# half.net
KiCad netlist of a schematic drawn in EAGLE
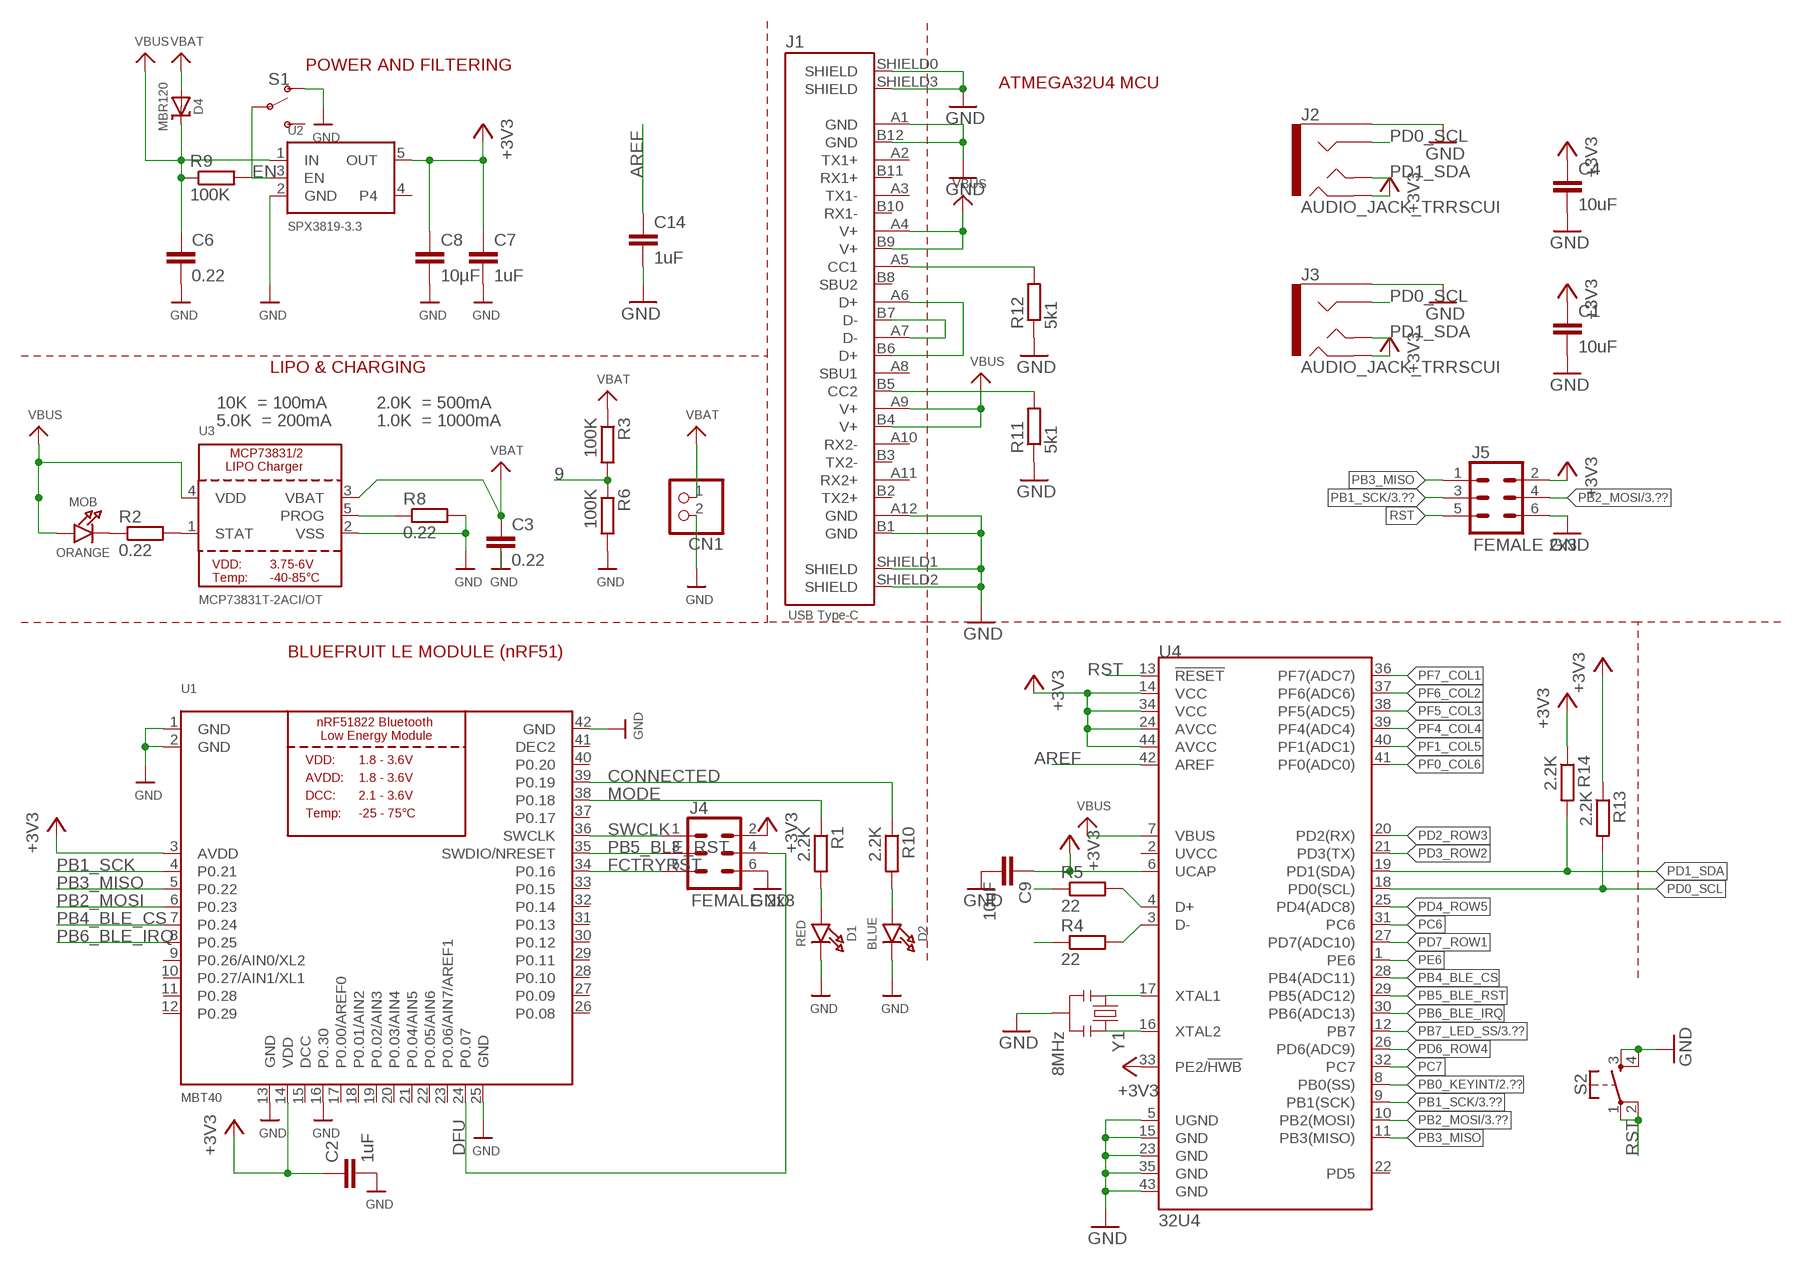
[diagram p0: schematic, sheet 1]
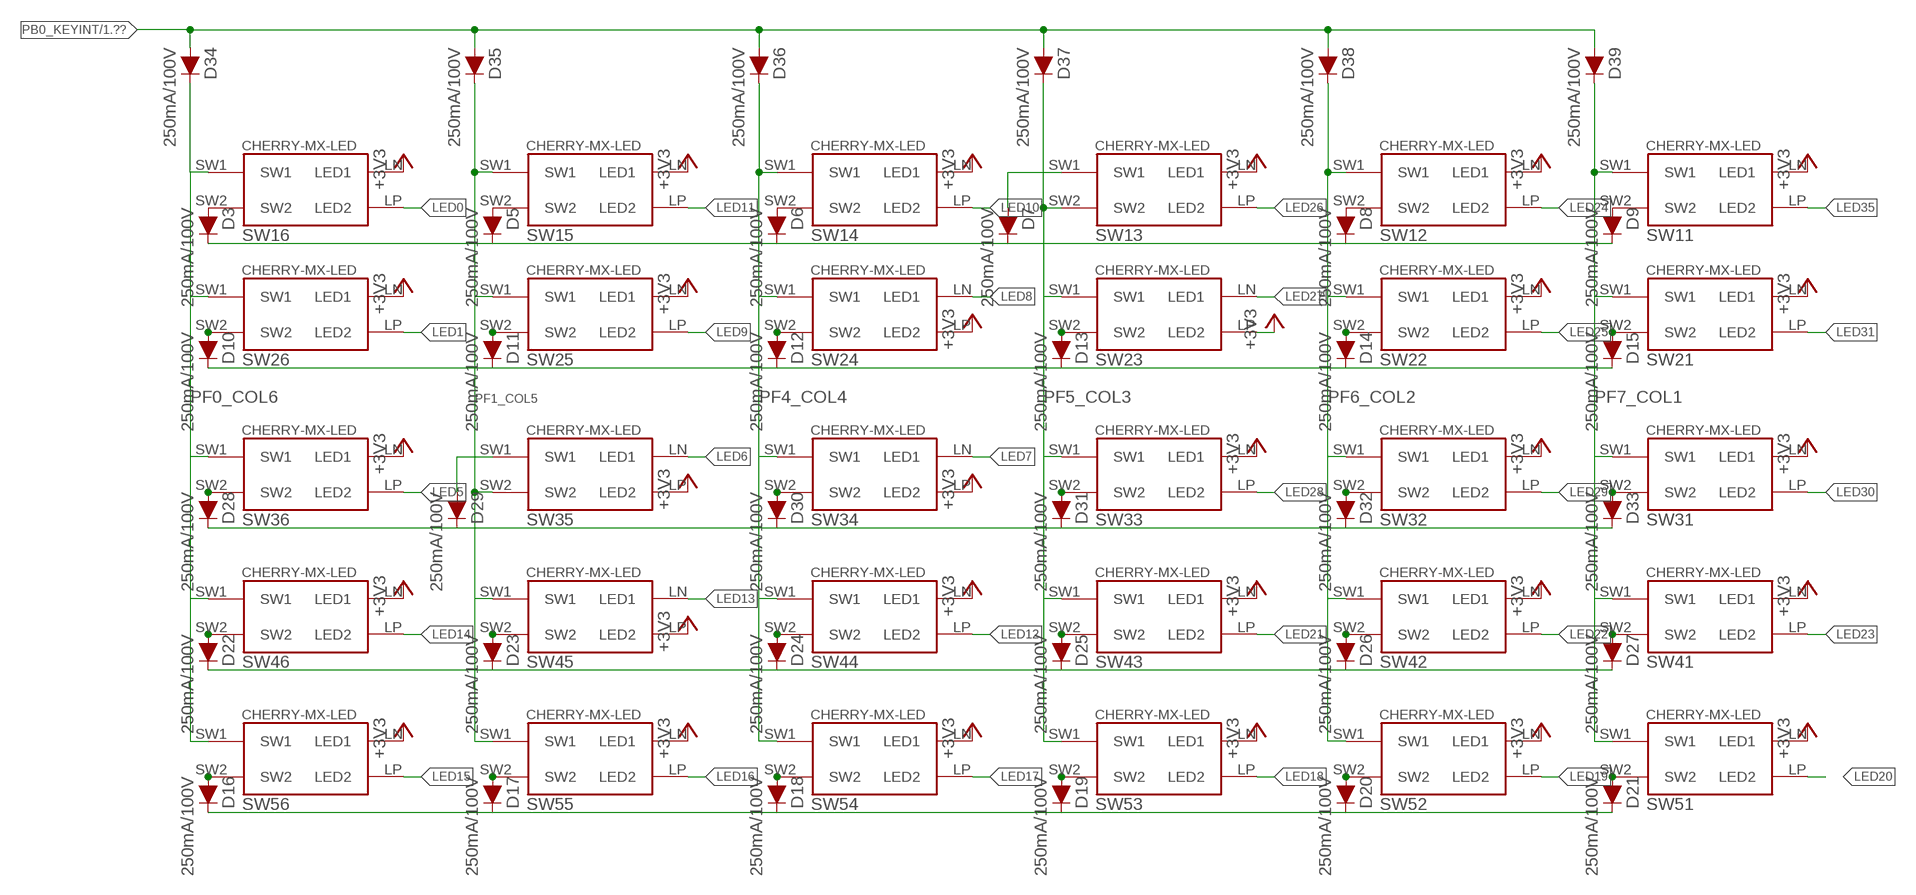
[diagram p1: schematic, sheet 2]
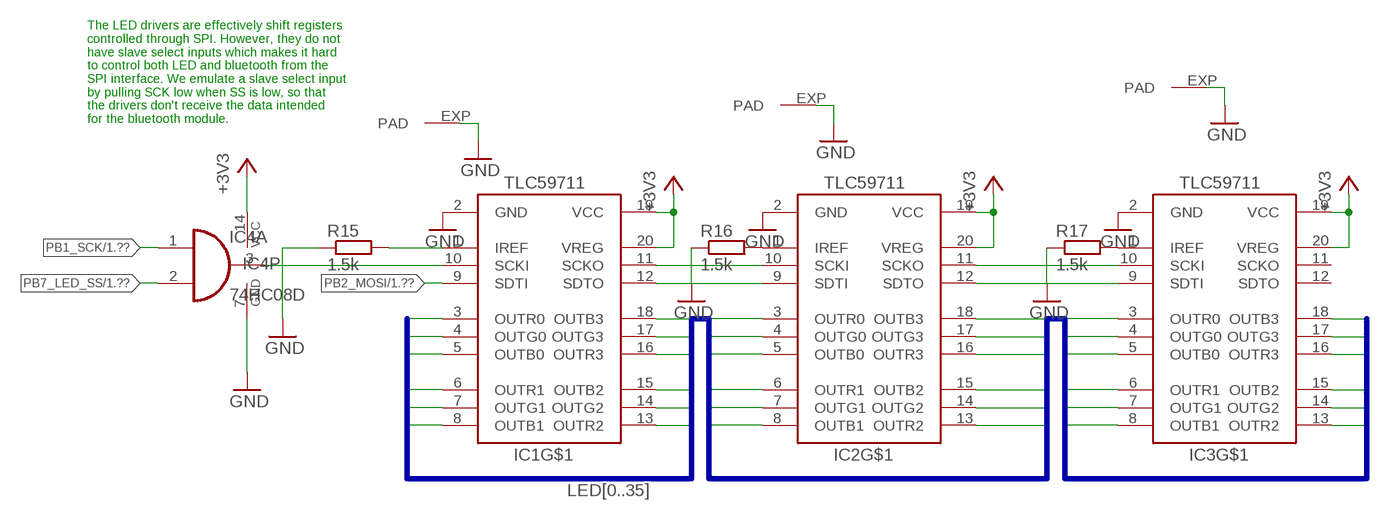
[diagram p2: schematic, sheet 3]

(export (version "E")
  (design (tool "Eeschema 10.0.6"))
  (components
    (comp (ref "D3")
      (value "250mA/100V")
      (footprint "eagle-import:SOD-323")
      (libsource (lib "eagle-import") (part "DIODE-BAS16J"))
    )
    (comp (ref "D5")
      (value "250mA/100V")
      (footprint "eagle-import:SOD-323")
      (libsource (lib "eagle-import") (part "DIODE-BAS16J"))
    )
    (comp (ref "D6")
      (value "250mA/100V")
      (footprint "eagle-import:SOD-323")
      (libsource (lib "eagle-import") (part "DIODE-BAS16J"))
    )
    (comp (ref "D7")
      (value "250mA/100V")
      (footprint "eagle-import:SOD-323")
      (libsource (lib "eagle-import") (part "DIODE-BAS16J"))
    )
    (comp (ref "D8")
      (value "250mA/100V")
      (footprint "eagle-import:SOD-323")
      (libsource (lib "eagle-import") (part "DIODE-BAS16J"))
    )
    (comp (ref "D9")
      (value "250mA/100V")
      (footprint "eagle-import:SOD-323")
      (libsource (lib "eagle-import") (part "DIODE-BAS16J"))
    )
    (comp (ref "D10")
      (value "250mA/100V")
      (footprint "eagle-import:SOD-323")
      (libsource (lib "eagle-import") (part "DIODE-BAS16J"))
    )
    (comp (ref "D11")
      (value "250mA/100V")
      (footprint "eagle-import:SOD-323")
      (libsource (lib "eagle-import") (part "DIODE-BAS16J"))
    )
    (comp (ref "D12")
      (value "250mA/100V")
      (footprint "eagle-import:SOD-323")
      (libsource (lib "eagle-import") (part "DIODE-BAS16J"))
    )
    (comp (ref "D13")
      (value "250mA/100V")
      (footprint "eagle-import:SOD-323")
      (libsource (lib "eagle-import") (part "DIODE-BAS16J"))
    )
    (comp (ref "D14")
      (value "250mA/100V")
      (footprint "eagle-import:SOD-323")
      (libsource (lib "eagle-import") (part "DIODE-BAS16J"))
    )
    (comp (ref "D15")
      (value "250mA/100V")
      (footprint "eagle-import:SOD-323")
      (libsource (lib "eagle-import") (part "DIODE-BAS16J"))
    )
    (comp (ref "D16")
      (value "250mA/100V")
      (footprint "eagle-import:SOD-323")
      (libsource (lib "eagle-import") (part "DIODE-BAS16J"))
    )
    (comp (ref "D17")
      (value "250mA/100V")
      (footprint "eagle-import:SOD-323")
      (libsource (lib "eagle-import") (part "DIODE-BAS16J"))
    )
    (comp (ref "D18")
      (value "250mA/100V")
      (footprint "eagle-import:SOD-323")
      (libsource (lib "eagle-import") (part "DIODE-BAS16J"))
    )
    (comp (ref "D19")
      (value "250mA/100V")
      (footprint "eagle-import:SOD-323")
      (libsource (lib "eagle-import") (part "DIODE-BAS16J"))
    )
    (comp (ref "D20")
      (value "250mA/100V")
      (footprint "eagle-import:SOD-323")
      (libsource (lib "eagle-import") (part "DIODE-BAS16J"))
    )
    (comp (ref "D21")
      (value "250mA/100V")
      (footprint "eagle-import:SOD-323")
      (libsource (lib "eagle-import") (part "DIODE-BAS16J"))
    )
    (comp (ref "D22")
      (value "250mA/100V")
      (footprint "eagle-import:SOD-323")
      (libsource (lib "eagle-import") (part "DIODE-BAS16J"))
    )
    (comp (ref "D23")
      (value "250mA/100V")
      (footprint "eagle-import:SOD-323")
      (libsource (lib "eagle-import") (part "DIODE-BAS16J"))
    )
    (comp (ref "D24")
      (value "250mA/100V")
      (footprint "eagle-import:SOD-323")
      (libsource (lib "eagle-import") (part "DIODE-BAS16J"))
    )
    (comp (ref "D25")
      (value "250mA/100V")
      (footprint "eagle-import:SOD-323")
      (libsource (lib "eagle-import") (part "DIODE-BAS16J"))
    )
    (comp (ref "D26")
      (value "250mA/100V")
      (footprint "eagle-import:SOD-323")
      (libsource (lib "eagle-import") (part "DIODE-BAS16J"))
    )
    (comp (ref "D27")
      (value "250mA/100V")
      (footprint "eagle-import:SOD-323")
      (libsource (lib "eagle-import") (part "DIODE-BAS16J"))
    )
    (comp (ref "D28")
      (value "250mA/100V")
      (footprint "eagle-import:SOD-323")
      (libsource (lib "eagle-import") (part "DIODE-BAS16J"))
    )
    (comp (ref "D29")
      (value "250mA/100V")
      (footprint "eagle-import:SOD-323")
      (libsource (lib "eagle-import") (part "DIODE-BAS16J"))
    )
    (comp (ref "D30")
      (value "250mA/100V")
      (footprint "eagle-import:SOD-323")
      (libsource (lib "eagle-import") (part "DIODE-BAS16J"))
    )
    (comp (ref "D31")
      (value "250mA/100V")
      (footprint "eagle-import:SOD-323")
      (libsource (lib "eagle-import") (part "DIODE-BAS16J"))
    )
    (comp (ref "D32")
      (value "250mA/100V")
      (footprint "eagle-import:SOD-323")
      (libsource (lib "eagle-import") (part "DIODE-BAS16J"))
    )
    (comp (ref "D33")
      (value "250mA/100V")
      (footprint "eagle-import:SOD-323")
      (libsource (lib "eagle-import") (part "DIODE-BAS16J"))
    )
    (comp (ref "D34")
      (value "250mA/100V")
      (footprint "eagle-import:SOD-323")
      (libsource (lib "eagle-import") (part "DIODE-BAS16J"))
    )
    (comp (ref "D35")
      (value "250mA/100V")
      (footprint "eagle-import:SOD-323")
      (libsource (lib "eagle-import") (part "DIODE-BAS16J"))
    )
    (comp (ref "D36")
      (value "250mA/100V")
      (footprint "eagle-import:SOD-323")
      (libsource (lib "eagle-import") (part "DIODE-BAS16J"))
    )
    (comp (ref "D37")
      (value "250mA/100V")
      (footprint "eagle-import:SOD-323")
      (libsource (lib "eagle-import") (part "DIODE-BAS16J"))
    )
    (comp (ref "D38")
      (value "250mA/100V")
      (footprint "eagle-import:SOD-323")
      (libsource (lib "eagle-import") (part "DIODE-BAS16J"))
    )
    (comp (ref "D39")
      (value "250mA/100V")
      (footprint "eagle-import:SOD-323")
      (libsource (lib "eagle-import") (part "DIODE-BAS16J"))
    )
    (comp (ref "SW11")
      (value "CHERRY-MX-LEDSMD")
      (footprint "eagle-import:CHERRY-MX-PM-SMDLED")
      (libsource (lib "eagle-import") (part "CHERRY-MX-LEDSMD"))
    )
    (comp (ref "SW12")
      (value "CHERRY-MX-LEDSMD")
      (footprint "eagle-import:CHERRY-MX-PM-SMDLED")
      (libsource (lib "eagle-import") (part "CHERRY-MX-LEDSMD"))
    )
    (comp (ref "SW13")
      (value "CHERRY-MX-LEDSMD")
      (footprint "eagle-import:CHERRY-MX-PM-SMDLED")
      (libsource (lib "eagle-import") (part "CHERRY-MX-LEDSMD"))
    )
    (comp (ref "SW14")
      (value "CHERRY-MX-LEDSMD")
      (footprint "eagle-import:CHERRY-MX-PM-SMDLED")
      (libsource (lib "eagle-import") (part "CHERRY-MX-LEDSMD"))
    )
    (comp (ref "SW15")
      (value "CHERRY-MX-LEDSMD")
      (footprint "eagle-import:CHERRY-MX-PM-SMDLED")
      (libsource (lib "eagle-import") (part "CHERRY-MX-LEDSMD"))
    )
    (comp (ref "SW16")
      (value "CHERRY-MX-LEDSMD")
      (footprint "eagle-import:CHERRY-MX-PM-SMDLED")
      (libsource (lib "eagle-import") (part "CHERRY-MX-LEDSMD"))
    )
    (comp (ref "SW21")
      (value "CHERRY-MX-LEDSMD")
      (footprint "eagle-import:CHERRY-MX-PM-SMDLED")
      (libsource (lib "eagle-import") (part "CHERRY-MX-LEDSMD"))
    )
    (comp (ref "SW22")
      (value "CHERRY-MX-LEDSMD")
      (footprint "eagle-import:CHERRY-MX-PM-SMDLED")
      (libsource (lib "eagle-import") (part "CHERRY-MX-LEDSMD"))
    )
    (comp (ref "SW23")
      (value "CHERRY-MX-LEDSMD")
      (footprint "eagle-import:CHERRY-MX-PM-SMDLED")
      (libsource (lib "eagle-import") (part "CHERRY-MX-LEDSMD"))
    )
    (comp (ref "SW24")
      (value "CHERRY-MX-LEDSMD")
      (footprint "eagle-import:CHERRY-MX-PM-SMDLED")
      (libsource (lib "eagle-import") (part "CHERRY-MX-LEDSMD"))
    )
    (comp (ref "SW25")
      (value "CHERRY-MX-LEDSMD")
      (footprint "eagle-import:CHERRY-MX-PM-SMDLED")
      (libsource (lib "eagle-import") (part "CHERRY-MX-LEDSMD"))
    )
    (comp (ref "SW26")
      (value "CHERRY-MX-LEDSMD")
      (footprint "eagle-import:CHERRY-MX-PM-SMDLED")
      (libsource (lib "eagle-import") (part "CHERRY-MX-LEDSMD"))
    )
    (comp (ref "SW31")
      (value "CHERRY-MX-LEDSMD")
      (footprint "eagle-import:CHERRY-MX-PM-SMDLED")
      (libsource (lib "eagle-import") (part "CHERRY-MX-LEDSMD"))
    )
    (comp (ref "SW32")
      (value "CHERRY-MX-LEDSMD")
      (footprint "eagle-import:CHERRY-MX-PM-SMDLED")
      (libsource (lib "eagle-import") (part "CHERRY-MX-LEDSMD"))
    )
    (comp (ref "SW33")
      (value "CHERRY-MX-LEDSMD")
      (footprint "eagle-import:CHERRY-MX-PM-SMDLED")
      (libsource (lib "eagle-import") (part "CHERRY-MX-LEDSMD"))
    )
    (comp (ref "SW34")
      (value "CHERRY-MX-LEDSMD")
      (footprint "eagle-import:CHERRY-MX-PM-SMDLED")
      (libsource (lib "eagle-import") (part "CHERRY-MX-LEDSMD"))
    )
    (comp (ref "SW35")
      (value "CHERRY-MX-LEDSMD")
      (footprint "eagle-import:CHERRY-MX-PM-SMDLED")
      (libsource (lib "eagle-import") (part "CHERRY-MX-LEDSMD"))
    )
    (comp (ref "SW36")
      (value "CHERRY-MX-LEDSMD")
      (footprint "eagle-import:CHERRY-MX-PM-SMDLED")
      (libsource (lib "eagle-import") (part "CHERRY-MX-LEDSMD"))
    )
    (comp (ref "SW41")
      (value "CHERRY-MX-LEDSMD")
      (footprint "eagle-import:CHERRY-MX-PM-SMDLED")
      (libsource (lib "eagle-import") (part "CHERRY-MX-LEDSMD"))
    )
    (comp (ref "SW42")
      (value "CHERRY-MX-LEDSMD")
      (footprint "eagle-import:CHERRY-MX-PM-SMDLED")
      (libsource (lib "eagle-import") (part "CHERRY-MX-LEDSMD"))
    )
    (comp (ref "SW43")
      (value "CHERRY-MX-LEDSMD")
      (footprint "eagle-import:CHERRY-MX-PM-SMDLED")
      (libsource (lib "eagle-import") (part "CHERRY-MX-LEDSMD"))
    )
    (comp (ref "SW44")
      (value "CHERRY-MX-LEDSMD")
      (footprint "eagle-import:CHERRY-MX-PM-SMDLED")
      (libsource (lib "eagle-import") (part "CHERRY-MX-LEDSMD"))
    )
    (comp (ref "SW45")
      (value "CHERRY-MX-LEDSMD")
      (footprint "eagle-import:CHERRY-MX-PM-SMDLED")
      (libsource (lib "eagle-import") (part "CHERRY-MX-LEDSMD"))
    )
    (comp (ref "SW46")
      (value "CHERRY-MX-LEDSMD")
      (footprint "eagle-import:CHERRY-MX-PM-SMDLED")
      (libsource (lib "eagle-import") (part "CHERRY-MX-LEDSMD"))
    )
    (comp (ref "SW51")
      (value "CHERRY-MX-LEDSMD")
      (footprint "eagle-import:CHERRY-MX-PM-SMDLED")
      (libsource (lib "eagle-import") (part "CHERRY-MX-LEDSMD"))
    )
    (comp (ref "SW52")
      (value "CHERRY-MX-LEDSMD")
      (footprint "eagle-import:CHERRY-MX-PM-SMDLED")
      (libsource (lib "eagle-import") (part "CHERRY-MX-LEDSMD"))
    )
    (comp (ref "SW53")
      (value "CHERRY-MX-LEDSMD")
      (footprint "eagle-import:CHERRY-MX-PM-SMDLED")
      (libsource (lib "eagle-import") (part "CHERRY-MX-LEDSMD"))
    )
    (comp (ref "SW54")
      (value "CHERRY-MX-LEDSMD")
      (footprint "eagle-import:CHERRY-MX-PM-SMDLED")
      (libsource (lib "eagle-import") (part "CHERRY-MX-LEDSMD"))
    )
    (comp (ref "SW55")
      (value "CHERRY-MX-LEDSMD")
      (footprint "eagle-import:CHERRY-MX-PM-SMDLED")
      (libsource (lib "eagle-import") (part "CHERRY-MX-LEDSMD"))
    )
    (comp (ref "SW56")
      (value "CHERRY-MX-LEDSMD")
      (footprint "eagle-import:CHERRY-MX-PM-SMDLED")
      (libsource (lib "eagle-import") (part "CHERRY-MX-LEDSMD"))
    )
    (comp (ref "IC1")
      (value "TLC59711")
      (footprint "eagle-import:HTSSOP20DAP")
      (libsource (lib "eagle-import") (part "TLC59711"))
    )
    (comp (ref "IC2")
      (value "TLC59711")
      (footprint "eagle-import:HTSSOP20DAP")
      (libsource (lib "eagle-import") (part "TLC59711"))
    )
    (comp (ref "IC3")
      (value "TLC59711")
      (footprint "eagle-import:HTSSOP20DAP")
      (libsource (lib "eagle-import") (part "TLC59711"))
    )
    (comp (ref "IC4")
      (value "74HC08D")
      (footprint "eagle-import:SO14")
      (libsource (lib "eagle-import") (part "7408DHC"))
    )
    (comp (ref "R15")
      (value "1.5k")
      (footprint "eagle-import:R0805")
      (libsource (lib "eagle-import") (part "R-EU_R0805"))
    )
    (comp (ref "R16")
      (value "1.5k")
      (footprint "eagle-import:R0805")
      (libsource (lib "eagle-import") (part "R-EU_R0805"))
    )
    (comp (ref "R17")
      (value "1.5k")
      (footprint "eagle-import:R0805")
      (libsource (lib "eagle-import") (part "R-EU_R0805"))
    )
    (comp (ref "C1")
      (value "10uF")
      (footprint "eagle-import:C0805")
      (libsource (lib "eagle-import") (part "C-EUC0805"))
    )
    (comp (ref "C2")
      (value "1uF")
      (footprint "eagle-import:C0805")
      (libsource (lib "eagle-import") (part "C-EUC0805"))
    )
    (comp (ref "C3")
      (value "0.22")
      (footprint "eagle-import:C0805")
      (libsource (lib "eagle-import") (part "C-EUC0805"))
    )
    (comp (ref "C4")
      (value "10uF")
      (footprint "eagle-import:C0805")
      (libsource (lib "eagle-import") (part "C-EUC0805"))
    )
    (comp (ref "C6")
      (value "0.22")
      (footprint "eagle-import:C0805")
      (libsource (lib "eagle-import") (part "C-EUC0805"))
    )
    (comp (ref "C7")
      (value "1uF")
      (footprint "eagle-import:C0805")
      (libsource (lib "eagle-import") (part "C-EUC0805"))
    )
    (comp (ref "C8")
      (value "10µF")
      (footprint "eagle-import:C0805")
      (libsource (lib "eagle-import") (part "C-EUC0805"))
    )
    (comp (ref "C9")
      (value "10uF")
      (footprint "eagle-import:C0805")
      (libsource (lib "eagle-import") (part "C-EUC0805"))
    )
    (comp (ref "C14")
      (value "1uF")
      (footprint "eagle-import:C0805")
      (libsource (lib "eagle-import") (part "C-EUC0805"))
    )
    (comp (ref "CN1")
      (value "JST_2PIN-SMT-RA")
      (footprint "eagle-import:JST-PH-2-SMT-RA")
      (libsource (lib "eagle-import") (part "JST_2PIN-SMT-RA"))
    )
    (comp (ref "D1")
      (value "RED")
      (footprint "eagle-import:CHIPLED_0805_NOOUTLINE")
      (libsource (lib "eagle-import") (part "LED0805_NOOUTLINE"))
    )
    (comp (ref "D2")
      (value "BLUE")
      (footprint "eagle-import:CHIPLED_0805_NOOUTLINE")
      (libsource (lib "eagle-import") (part "LED0805_NOOUTLINE"))
    )
    (comp (ref "D4")
      (value "MBR120")
      (footprint "eagle-import:SOD-123")
      (libsource (lib "eagle-import") (part "DIODE-SCHOTTKYSOD-123"))
    )
    (comp (ref "J1")
      (value "DX07S024JJ2_USB_TYPE-C")
      (footprint "eagle-import:DX07S0224JJ2_USB-C")
      (fields (field (name "MANF") "USB Type-C DX07 Series Receptacle"))
      (libsource (lib "eagle-import") (part "DX07S024JJ2_USB_TYPE-C"))
    )
    (comp (ref "J2")
      (value "AUDIO_JACK_TRRSCUI")
      (footprint "eagle-import:AUDIO_JACK_3.5MM_TRRS_SMD_CUI")
      (libsource (lib "eagle-import") (part "AUDIO_JACK_TRRSCUI"))
    )
    (comp (ref "J3")
      (value "AUDIO_JACK_TRRSCUI")
      (footprint "eagle-import:AUDIO_JACK_3.5MM_TRRS_SMD_CUI")
      (libsource (lib "eagle-import") (part "AUDIO_JACK_TRRSCUI"))
    )
    (comp (ref "J4")
      (value "FEMALE 2x3")
      (footprint "eagle-import:2X3")
      (libsource (lib "eagle-import") (part "CONN_03X2FEMALE"))
    )
    (comp (ref "J5")
      (value "FEMALE 2x3")
      (footprint "eagle-import:2X3")
      (libsource (lib "eagle-import") (part "CONN_03X2FEMALE"))
    )
    (comp (ref "MOB")
      (value "ORANGE")
      (footprint "eagle-import:CHIPLED_0805_NOOUTLINE")
      (libsource (lib "eagle-import") (part "LED0805_NOOUTLINE"))
    )
    (comp (ref "R1")
      (value "2.2K")
      (footprint "eagle-import:R0805")
      (libsource (lib "eagle-import") (part "R-EU_R0805"))
    )
    (comp (ref "R2")
      (value "0.22")
      (footprint "eagle-import:R0805")
      (libsource (lib "eagle-import") (part "R-EU_R0805"))
    )
    (comp (ref "R3")
      (value "100K")
      (footprint "eagle-import:R0805")
      (libsource (lib "eagle-import") (part "R-EU_R0805"))
    )
    (comp (ref "R4")
      (value "22")
      (footprint "eagle-import:R0805")
      (libsource (lib "eagle-import") (part "R-EU_R0805"))
    )
    (comp (ref "R5")
      (value "22")
      (footprint "eagle-import:R0805")
      (libsource (lib "eagle-import") (part "R-EU_R0805"))
    )
    (comp (ref "R6")
      (value "100K")
      (footprint "eagle-import:R0805")
      (libsource (lib "eagle-import") (part "R-EU_R0805"))
    )
    (comp (ref "R8")
      (value "0.22")
      (footprint "eagle-import:R0805")
      (libsource (lib "eagle-import") (part "R-EU_R0805"))
    )
    (comp (ref "R9")
      (value "100K")
      (footprint "eagle-import:R0805")
      (libsource (lib "eagle-import") (part "R-EU_R0805"))
    )
    (comp (ref "R10")
      (value "2.2K")
      (footprint "eagle-import:R0805")
      (libsource (lib "eagle-import") (part "R-EU_R0805"))
    )
    (comp (ref "R11")
      (value "5k1")
      (footprint "eagle-import:R0805")
      (libsource (lib "eagle-import") (part "R-EU_R0805"))
    )
    (comp (ref "R12")
      (value "5k1")
      (footprint "eagle-import:R0805")
      (libsource (lib "eagle-import") (part "R-EU_R0805"))
    )
    (comp (ref "R13")
      (value "2.2K")
      (footprint "eagle-import:R0805")
      (libsource (lib "eagle-import") (part "R-EU_R0805"))
    )
    (comp (ref "R14")
      (value "2.2K")
      (footprint "eagle-import:R0805")
      (libsource (lib "eagle-import") (part "R-EU_R0805"))
    )
    (comp (ref "S1")
      (value "SWITCH-SPDT-SMD-RIGHT-ANGLE")
      (footprint "eagle-import:SWITCH_SPST_SMD_A")
      (libsource (lib "eagle-import") (part "SWITCH-SPDT-SMD-RIGHT-ANGLE"))
    )
    (comp (ref "S2")
      (value "MOMENTARY-SWITCH-SPST-2-SMD-5.2MM")
      (footprint "eagle-import:TACTILE_SWITCH_SMD_5.2MM")
      (libsource (lib "eagle-import") (part "MOMENTARY-SWITCH-SPST-2-SMD-5.2MM"))
    )
    (comp (ref "U1")
      (value "MBT40")
      (footprint "eagle-import:BLE_MODULE_RAYTAC_MDBT40")
      (libsource (lib "eagle-import") (part "NRF51822_MODULE_MDBT40"))
    )
    (comp (ref "U2")
      (value "SPX3819-3.3")
      (footprint "eagle-import:SOT23-5")
      (libsource (lib "eagle-import") (part "VREG_SOT23-5"))
    )
    (comp (ref "U3")
      (value "MCP73831T-2ACI/OT")
      (footprint "eagle-import:SOT23-5")
      (libsource (lib "eagle-import") (part "MCP73831/2"))
    )
    (comp (ref "U4")
      (value "32U4")
      (footprint "eagle-import:TQFP44")
      (libsource (lib "eagle-import") (part "ATMEGA32U4TQFP-44"))
    )
    (comp (ref "Y1")
      (value "8MHz")
      (footprint "eagle-import:RESONATOR-SMD")
      (libsource (lib "eagle-import") (part "RESONATORSMD"))
    )
  )
  (nets
    (net (code "7") (name "+3V3") (class "Default")
      (node (ref "C1") (pin "1") (pinfunction "1_1") (pintype "passive"))
      (node (ref "C2") (pin "1") (pinfunction "1_1") (pintype "passive"))
      (node (ref "C4") (pin "1") (pinfunction "1_1") (pintype "passive"))
      (node (ref "C7") (pin "1") (pinfunction "1_1") (pintype "passive"))
      (node (ref "C8") (pin "1") (pinfunction "1_1") (pintype "passive"))
      (node (ref "C9") (pin "1") (pinfunction "1_1") (pintype "passive"))
      (node (ref "IC1") (pin "19") (pinfunction "VCC_19") (pintype "power_in"))
      (node (ref "IC1") (pin "20") (pinfunction "VREG_20") (pintype "bidirectional"))
      (node (ref "IC2") (pin "19") (pinfunction "VCC_19") (pintype "power_in"))
      (node (ref "IC2") (pin "20") (pinfunction "VREG_20") (pintype "bidirectional"))
      (node (ref "IC3") (pin "19") (pinfunction "VCC_19") (pintype "power_in"))
      (node (ref "IC3") (pin "20") (pinfunction "VREG_20") (pintype "bidirectional"))
      (node (ref "IC4") (pin "14") (pinfunction "VCC_14") (pintype "power_in"))
      (node (ref "J2") (pin "RING2") (pinfunction "RING2_RING2") (pintype "bidirectional"))
      (node (ref "J3") (pin "RING2") (pinfunction "RING2_RING2") (pintype "bidirectional"))
      (node (ref "J4") (pin "2") (pinfunction "2_2") (pintype "bidirectional"))
      (node (ref "J5") (pin "2") (pinfunction "2_2") (pintype "bidirectional"))
      (node (ref "R13") (pin "1") (pinfunction "1_1") (pintype "passive"))
      (node (ref "R14") (pin "1") (pinfunction "1_1") (pintype "passive"))
      (node (ref "SW11") (pin "LN") (pinfunction "LED1_LN") (pintype "bidirectional"))
      (node (ref "SW12") (pin "LN") (pinfunction "LED1_LN") (pintype "bidirectional"))
      (node (ref "SW13") (pin "LN") (pinfunction "LED1_LN") (pintype "bidirectional"))
      (node (ref "SW14") (pin "LN") (pinfunction "LED1_LN") (pintype "bidirectional"))
      (node (ref "SW15") (pin "LN") (pinfunction "LED1_LN") (pintype "bidirectional"))
      (node (ref "SW16") (pin "LN") (pinfunction "LED1_LN") (pintype "bidirectional"))
      (node (ref "SW21") (pin "LN") (pinfunction "LED1_LN") (pintype "bidirectional"))
      (node (ref "SW22") (pin "LN") (pinfunction "LED1_LN") (pintype "bidirectional"))
      (node (ref "SW23") (pin "LP") (pinfunction "LED2_LP") (pintype "bidirectional"))
      (node (ref "SW24") (pin "LP") (pinfunction "LED2_LP") (pintype "bidirectional"))
      (node (ref "SW25") (pin "LN") (pinfunction "LED1_LN") (pintype "bidirectional"))
      (node (ref "SW26") (pin "LN") (pinfunction "LED1_LN") (pintype "bidirectional"))
      (node (ref "SW31") (pin "LN") (pinfunction "LED1_LN") (pintype "bidirectional"))
      (node (ref "SW32") (pin "LN") (pinfunction "LED1_LN") (pintype "bidirectional"))
      (node (ref "SW33") (pin "LN") (pinfunction "LED1_LN") (pintype "bidirectional"))
      (node (ref "SW34") (pin "LP") (pinfunction "LED2_LP") (pintype "bidirectional"))
      (node (ref "SW35") (pin "LP") (pinfunction "LED2_LP") (pintype "bidirectional"))
      (node (ref "SW36") (pin "LN") (pinfunction "LED1_LN") (pintype "bidirectional"))
      (node (ref "SW41") (pin "LN") (pinfunction "LED1_LN") (pintype "bidirectional"))
      (node (ref "SW42") (pin "LN") (pinfunction "LED1_LN") (pintype "bidirectional"))
      (node (ref "SW43") (pin "LN") (pinfunction "LED1_LN") (pintype "bidirectional"))
      (node (ref "SW44") (pin "LN") (pinfunction "LED1_LN") (pintype "bidirectional"))
      (node (ref "SW45") (pin "LP") (pinfunction "LED2_LP") (pintype "bidirectional"))
      (node (ref "SW46") (pin "LN") (pinfunction "LED1_LN") (pintype "bidirectional"))
      (node (ref "SW51") (pin "LN") (pinfunction "LED1_LN") (pintype "bidirectional"))
      (node (ref "SW52") (pin "LN") (pinfunction "LED1_LN") (pintype "bidirectional"))
      (node (ref "SW53") (pin "LN") (pinfunction "LED1_LN") (pintype "bidirectional"))
      (node (ref "SW54") (pin "LN") (pinfunction "LED1_LN") (pintype "bidirectional"))
      (node (ref "SW55") (pin "LN") (pinfunction "LED1_LN") (pintype "bidirectional"))
      (node (ref "SW56") (pin "LN") (pinfunction "LED1_LN") (pintype "bidirectional"))
      (node (ref "U1") (pin "14") (pinfunction "VDD_14") (pintype "power_in"))
      (node (ref "U1") (pin "3") (pinfunction "AVDD_3") (pintype "power_in"))
      (node (ref "U2") (pin "5") (pinfunction "OUT_5") (pintype "power_in"))
      (node (ref "U4") (pin "14") (pinfunction "VCC_14") (pintype "bidirectional"))
      (node (ref "U4") (pin "24") (pinfunction "AVCC_24") (pintype "bidirectional"))
      (node (ref "U4") (pin "33") (pinfunction "PE2/~{HWB}_33") (pintype "bidirectional"))
      (node (ref "U4") (pin "34") (pinfunction "VCC_34") (pintype "bidirectional"))
      (node (ref "U4") (pin "44") (pinfunction "AVCC_44") (pintype "bidirectional"))
      (node (ref "U4") (pin "6") (pinfunction "UCAP_6") (pintype "bidirectional"))
    )
    (net (code "9") (name "9") (class "Default")
      (node (ref "R3") (pin "2") (pinfunction "2_2") (pintype "passive"))
      (node (ref "R6") (pin "1") (pinfunction "1_1") (pintype "passive"))
    )
    (net (code "10") (name "AREF") (class "Default")
      (node (ref "C14") (pin "1") (pinfunction "1_1") (pintype "passive"))
      (node (ref "U4") (pin "42") (pinfunction "AREF_42") (pintype "bidirectional"))
    )
    (net (code "11") (name "CONNECTED") (class "Default")
      (node (ref "R10") (pin "1") (pinfunction "1_1") (pintype "passive"))
      (node (ref "U1") (pin "39") (pinfunction "P0.19_39") (pintype "bidirectional"))
    )
    (net (code "12") (name "D++") (class "Default")
      (node (ref "J1") (pin "A6") (pinfunction "D+_A6") (pintype "bidirectional"))
      (node (ref "J1") (pin "B6") (pinfunction "D+_B6") (pintype "bidirectional"))
      (node (ref "R5") (pin "1") (pinfunction "1_1") (pintype "passive"))
    )
    (net (code "13") (name "D--") (class "Default")
      (node (ref "J1") (pin "A7") (pinfunction "D-_A7") (pintype "bidirectional"))
      (node (ref "J1") (pin "B7") (pinfunction "D-_B7") (pintype "bidirectional"))
      (node (ref "R4") (pin "1") (pinfunction "1_1") (pintype "passive"))
    )
    (net (code "14") (name "DCC") (class "Default")
      (node (ref "U1") (pin "15") (pinfunction "DCC_15") (pintype "power_in"))
    )
    (net (code "15") (name "DEC2") (class "Default")
      (node (ref "U1") (pin "41") (pinfunction "DEC2_41") (pintype "power_in"))
    )
    (net (code "16") (name "DFU") (class "Default")
      (node (ref "J4") (pin "4") (pinfunction "4_4") (pintype "bidirectional"))
      (node (ref "U1") (pin "24") (pinfunction "P0.07_24") (pintype "bidirectional"))
    )
    (net (code "17") (name "EN") (class "Default")
      (node (ref "R9") (pin "2") (pinfunction "2_2") (pintype "passive"))
      (node (ref "S1") (pin "2") (pinfunction "P_2") (pintype "passive"))
      (node (ref "U2") (pin "3") (pinfunction "EN_3") (pintype "input"))
    )
    (net (code "18") (name "FCTRYRST") (class "Default")
      (node (ref "J4") (pin "5") (pinfunction "5_5") (pintype "bidirectional"))
      (node (ref "U1") (pin "34") (pinfunction "P0.16_34") (pintype "bidirectional"))
    )
    (net (code "19") (name "GND") (class "Default")
      (node (ref "C1") (pin "2") (pinfunction "2_2") (pintype "passive"))
      (node (ref "C14") (pin "2") (pinfunction "2_2") (pintype "passive"))
      (node (ref "C2") (pin "2") (pinfunction "2_2") (pintype "passive"))
      (node (ref "C3") (pin "2") (pinfunction "2_2") (pintype "passive"))
      (node (ref "C4") (pin "2") (pinfunction "2_2") (pintype "passive"))
      (node (ref "C6") (pin "2") (pinfunction "2_2") (pintype "passive"))
      (node (ref "C7") (pin "2") (pinfunction "2_2") (pintype "passive"))
      (node (ref "C8") (pin "2") (pinfunction "2_2") (pintype "passive"))
      (node (ref "C9") (pin "2") (pinfunction "2_2") (pintype "passive"))
      (node (ref "CN1") (pin "2") (pinfunction "1_2") (pintype "passive"))
      (node (ref "D1") (pin "C") (pinfunction "C_C") (pintype "passive"))
      (node (ref "D2") (pin "C") (pinfunction "C_C") (pintype "passive"))
      (node (ref "IC1") (pin "2") (pinfunction "GND_2") (pintype "power_in"))
      (node (ref "IC1") (pin "EXP") (pinfunction "PAD_EXP") (pintype "passive"))
      (node (ref "IC2") (pin "2") (pinfunction "GND_2") (pintype "power_in"))
      (node (ref "IC2") (pin "EXP") (pinfunction "PAD_EXP") (pintype "passive"))
      (node (ref "IC3") (pin "2") (pinfunction "GND_2") (pintype "power_in"))
      (node (ref "IC3") (pin "EXP") (pinfunction "PAD_EXP") (pintype "passive"))
      (node (ref "IC4") (pin "7") (pinfunction "GND_7") (pintype "power_in"))
      (node (ref "J1") (pin "A1") (pinfunction "GND_A1") (pintype "power_in"))
      (node (ref "J1") (pin "A12") (pinfunction "GND_A12") (pintype "power_in"))
      (node (ref "J1") (pin "B1") (pinfunction "GND_B1") (pintype "power_in"))
      (node (ref "J1") (pin "B12") (pinfunction "GND_B12") (pintype "power_in"))
      (node (ref "J1") (pin "SHIELD0") (pinfunction "SHIELD_SHIELD0") (pintype "bidirectional"))
      (node (ref "J1") (pin "SHIELD1") (pinfunction "SHIELD_SHIELD1") (pintype "bidirectional"))
      (node (ref "J1") (pin "SHIELD2") (pinfunction "SHIELD_SHIELD2") (pintype "bidirectional"))
      (node (ref "J1") (pin "SHIELD3") (pinfunction "SHIELD_SHIELD3") (pintype "bidirectional"))
      (node (ref "J2") (pin "EARTH") (pinfunction "EARTH_EARTH") (pintype "bidirectional"))
      (node (ref "J3") (pin "EARTH") (pinfunction "EARTH_EARTH") (pintype "bidirectional"))
      (node (ref "J4") (pin "6") (pinfunction "6_6") (pintype "bidirectional"))
      (node (ref "J5") (pin "6") (pinfunction "6_6") (pintype "bidirectional"))
      (node (ref "R11") (pin "1") (pinfunction "1_1") (pintype "passive"))
      (node (ref "R12") (pin "1") (pinfunction "1_1") (pintype "passive"))
      (node (ref "R15") (pin "1") (pinfunction "1_1") (pintype "passive"))
      (node (ref "R16") (pin "1") (pinfunction "1_1") (pintype "passive"))
      (node (ref "R17") (pin "1") (pinfunction "1_1") (pintype "passive"))
      (node (ref "R6") (pin "2") (pinfunction "2_2") (pintype "passive"))
      (node (ref "R8") (pin "2") (pinfunction "2_2") (pintype "passive"))
      (node (ref "S1") (pin "1") (pinfunction "O_1") (pintype "passive"))
      (node (ref "S2") (pin "3") (pinfunction "3_3") (pintype "passive"))
      (node (ref "S2") (pin "4") (pinfunction "4_4") (pintype "passive"))
      (node (ref "U1") (pin "1") (pinfunction "GND_1") (pintype "power_in"))
      (node (ref "U1") (pin "13") (pinfunction "GND_13") (pintype "power_in"))
      (node (ref "U1") (pin "16") (pinfunction "P0.30_16") (pintype "bidirectional"))
      (node (ref "U1") (pin "2") (pinfunction "GND_2") (pintype "power_in"))
      (node (ref "U1") (pin "25") (pinfunction "GND_25") (pintype "power_in"))
      (node (ref "U1") (pin "42") (pinfunction "GND_42") (pintype "power_in"))
      (node (ref "U2") (pin "2") (pinfunction "GND_2") (pintype "power_in"))
      (node (ref "U3") (pin "2") (pinfunction "VSS_2") (pintype "power_in"))
      (node (ref "U4") (pin "15") (pinfunction "GND_15") (pintype "bidirectional"))
      (node (ref "U4") (pin "23") (pinfunction "GND_23") (pintype "bidirectional"))
      (node (ref "U4") (pin "35") (pinfunction "GND_35") (pintype "bidirectional"))
      (node (ref "U4") (pin "43") (pinfunction "GND_43") (pintype "bidirectional"))
      (node (ref "U4") (pin "5") (pinfunction "UGND_5") (pintype "bidirectional"))
      (node (ref "Y1") (pin "2") (pinfunction "2_2") (pintype "passive"))
    )
    (net (code "20") (name "LED0") (class "Default")
      (node (ref "IC1") (pin "3") (pinfunction "OUTR0_3") (pintype "open_collector"))
      (node (ref "SW16") (pin "LP") (pinfunction "LED2_LP") (pintype "bidirectional"))
    )
    (net (code "21") (name "LED1") (class "Default")
      (node (ref "IC1") (pin "4") (pinfunction "OUTG0_4") (pintype "open_collector"))
      (node (ref "SW26") (pin "LP") (pinfunction "LED2_LP") (pintype "bidirectional"))
    )
    (net (code "22") (name "LED5") (class "Default")
      (node (ref "IC1") (pin "8") (pinfunction "OUTB1_8") (pintype "open_collector"))
      (node (ref "SW36") (pin "LP") (pinfunction "LED2_LP") (pintype "bidirectional"))
    )
    (net (code "23") (name "LED6") (class "Default")
      (node (ref "IC1") (pin "13") (pinfunction "OUTR2_13") (pintype "open_collector"))
      (node (ref "SW35") (pin "LN") (pinfunction "LED1_LN") (pintype "bidirectional"))
    )
    (net (code "24") (name "LED7") (class "Default")
      (node (ref "IC1") (pin "14") (pinfunction "OUTG2_14") (pintype "open_collector"))
      (node (ref "SW34") (pin "LN") (pinfunction "LED1_LN") (pintype "bidirectional"))
    )
    (net (code "25") (name "LED8") (class "Default")
      (node (ref "IC1") (pin "15") (pinfunction "OUTB2_15") (pintype "open_collector"))
      (node (ref "SW24") (pin "LN") (pinfunction "LED1_LN") (pintype "bidirectional"))
    )
    (net (code "26") (name "LED9") (class "Default")
      (node (ref "IC1") (pin "16") (pinfunction "OUTR3_16") (pintype "open_collector"))
      (node (ref "SW25") (pin "LP") (pinfunction "LED2_LP") (pintype "bidirectional"))
    )
    (net (code "27") (name "LED10") (class "Default")
      (node (ref "IC1") (pin "17") (pinfunction "OUTG3_17") (pintype "open_collector"))
      (node (ref "SW14") (pin "LP") (pinfunction "LED2_LP") (pintype "bidirectional"))
    )
    (net (code "28") (name "LED11") (class "Default")
      (node (ref "IC1") (pin "18") (pinfunction "OUTB3_18") (pintype "open_collector"))
      (node (ref "SW15") (pin "LP") (pinfunction "LED2_LP") (pintype "bidirectional"))
    )
    (net (code "29") (name "LED12") (class "Default")
      (node (ref "IC2") (pin "3") (pinfunction "OUTR0_3") (pintype "open_collector"))
      (node (ref "SW44") (pin "LP") (pinfunction "LED2_LP") (pintype "bidirectional"))
    )
    (net (code "30") (name "LED13") (class "Default")
      (node (ref "IC2") (pin "4") (pinfunction "OUTG0_4") (pintype "open_collector"))
      (node (ref "SW45") (pin "LN") (pinfunction "LED1_LN") (pintype "bidirectional"))
    )
    (net (code "31") (name "LED14") (class "Default")
      (node (ref "IC2") (pin "5") (pinfunction "OUTB0_5") (pintype "open_collector"))
      (node (ref "SW46") (pin "LP") (pinfunction "LED2_LP") (pintype "bidirectional"))
    )
    (net (code "32") (name "LED15") (class "Default")
      (node (ref "IC2") (pin "6") (pinfunction "OUTR1_6") (pintype "open_collector"))
      (node (ref "SW56") (pin "LP") (pinfunction "LED2_LP") (pintype "bidirectional"))
    )
    (net (code "33") (name "LED16") (class "Default")
      (node (ref "IC2") (pin "7") (pinfunction "OUTG1_7") (pintype "open_collector"))
      (node (ref "SW55") (pin "LP") (pinfunction "LED2_LP") (pintype "bidirectional"))
    )
    (net (code "34") (name "LED17") (class "Default")
      (node (ref "IC2") (pin "8") (pinfunction "OUTB1_8") (pintype "open_collector"))
      (node (ref "SW54") (pin "LP") (pinfunction "LED2_LP") (pintype "bidirectional"))
    )
    (net (code "35") (name "LED18") (class "Default")
      (node (ref "IC2") (pin "13") (pinfunction "OUTR2_13") (pintype "open_collector"))
      (node (ref "SW53") (pin "LP") (pinfunction "LED2_LP") (pintype "bidirectional"))
    )
    (net (code "36") (name "LED19") (class "Default")
      (node (ref "IC2") (pin "14") (pinfunction "OUTG2_14") (pintype "open_collector"))
      (node (ref "SW52") (pin "LP") (pinfunction "LED2_LP") (pintype "bidirectional"))
    )
    (net (code "37") (name "LED20") (class "Default")
      (node (ref "IC2") (pin "15") (pinfunction "OUTB2_15") (pintype "open_collector"))
      (node (ref "SW51") (pin "LP") (pinfunction "LED2_LP") (pintype "bidirectional"))
    )
    (net (code "38") (name "LED21") (class "Default")
      (node (ref "IC2") (pin "16") (pinfunction "OUTR3_16") (pintype "open_collector"))
      (node (ref "SW43") (pin "LP") (pinfunction "LED2_LP") (pintype "bidirectional"))
    )
    (net (code "39") (name "LED22") (class "Default")
      (node (ref "IC2") (pin "17") (pinfunction "OUTG3_17") (pintype "open_collector"))
      (node (ref "SW42") (pin "LP") (pinfunction "LED2_LP") (pintype "bidirectional"))
    )
    (net (code "40") (name "LED23") (class "Default")
      (node (ref "IC2") (pin "18") (pinfunction "OUTB3_18") (pintype "open_collector"))
      (node (ref "SW41") (pin "LP") (pinfunction "LED2_LP") (pintype "bidirectional"))
    )
    (net (code "41") (name "LED24") (class "Default")
      (node (ref "IC3") (pin "3") (pinfunction "OUTR0_3") (pintype "open_collector"))
      (node (ref "SW12") (pin "LP") (pinfunction "LED2_LP") (pintype "bidirectional"))
    )
    (net (code "42") (name "LED25") (class "Default")
      (node (ref "IC3") (pin "4") (pinfunction "OUTG0_4") (pintype "open_collector"))
      (node (ref "SW22") (pin "LP") (pinfunction "LED2_LP") (pintype "bidirectional"))
    )
    (net (code "43") (name "LED26") (class "Default")
      (node (ref "IC3") (pin "5") (pinfunction "OUTB0_5") (pintype "open_collector"))
      (node (ref "SW13") (pin "LP") (pinfunction "LED2_LP") (pintype "bidirectional"))
    )
    (net (code "44") (name "LED27") (class "Default")
      (node (ref "IC3") (pin "6") (pinfunction "OUTR1_6") (pintype "open_collector"))
      (node (ref "SW23") (pin "LN") (pinfunction "LED1_LN") (pintype "bidirectional"))
    )
    (net (code "45") (name "LED28") (class "Default")
      (node (ref "IC3") (pin "7") (pinfunction "OUTG1_7") (pintype "open_collector"))
      (node (ref "SW33") (pin "LP") (pinfunction "LED2_LP") (pintype "bidirectional"))
    )
    (net (code "46") (name "LED29") (class "Default")
      (node (ref "IC3") (pin "8") (pinfunction "OUTB1_8") (pintype "open_collector"))
      (node (ref "SW32") (pin "LP") (pinfunction "LED2_LP") (pintype "bidirectional"))
    )
    (net (code "47") (name "LED30") (class "Default")
      (node (ref "IC3") (pin "13") (pinfunction "OUTR2_13") (pintype "open_collector"))
      (node (ref "SW31") (pin "LP") (pinfunction "LED2_LP") (pintype "bidirectional"))
    )
    (net (code "48") (name "LED31") (class "Default")
      (node (ref "IC3") (pin "14") (pinfunction "OUTG2_14") (pintype "open_collector"))
      (node (ref "SW21") (pin "LP") (pinfunction "LED2_LP") (pintype "bidirectional"))
    )
    (net (code "49") (name "LED35") (class "Default")
      (node (ref "IC3") (pin "18") (pinfunction "OUTB3_18") (pintype "open_collector"))
      (node (ref "SW11") (pin "LP") (pinfunction "LED2_LP") (pintype "bidirectional"))
    )
    (net (code "50") (name "MODE") (class "Default")
      (node (ref "R1") (pin "1") (pinfunction "1_1") (pintype "passive"))
      (node (ref "U1") (pin "38") (pinfunction "P0.18_38") (pintype "bidirectional"))
    )
    (net (code "51") (name "Net-(D1-PadA)") (class "Default")
      (node (ref "D1") (pin "A") (pinfunction "A_A") (pintype "passive"))
      (node (ref "R1") (pin "2") (pinfunction "2_2") (pintype "passive"))
    )
    (net (code "52") (name "Net-(D2-PadA)") (class "Default")
      (node (ref "D2") (pin "A") (pinfunction "A_A") (pintype "passive"))
      (node (ref "R10") (pin "2") (pinfunction "2_2") (pintype "passive"))
    )
    (net (code "53") (name "Net-(D3-PadA)") (class "Default")
      (node (ref "D3") (pin "A") (pinfunction "A_A") (pintype "passive"))
      (node (ref "SW16") (pin "SW2") (pinfunction "SW2_SW2") (pintype "bidirectional"))
    )
    (net (code "54") (name "Net-(D5-PadA)") (class "Default")
      (node (ref "D5") (pin "A") (pinfunction "A_A") (pintype "passive"))
      (node (ref "SW15") (pin "SW2") (pinfunction "SW2_SW2") (pintype "bidirectional"))
    )
    (net (code "55") (name "Net-(D6-PadA)") (class "Default")
      (node (ref "D6") (pin "A") (pinfunction "A_A") (pintype "passive"))
      (node (ref "SW14") (pin "SW2") (pinfunction "SW2_SW2") (pintype "bidirectional"))
    )
    (net (code "56") (name "Net-(D7-PadA)") (class "Default")
      (node (ref "D7") (pin "A") (pinfunction "A_A") (pintype "passive"))
      (node (ref "SW13") (pin "SW1") (pinfunction "SW1_SW1") (pintype "bidirectional"))
    )
    (net (code "57") (name "Net-(D8-PadA)") (class "Default")
      (node (ref "D8") (pin "A") (pinfunction "A_A") (pintype "passive"))
      (node (ref "SW12") (pin "SW2") (pinfunction "SW2_SW2") (pintype "bidirectional"))
    )
    (net (code "58") (name "Net-(D9-PadA)") (class "Default")
      (node (ref "D9") (pin "A") (pinfunction "A_A") (pintype "passive"))
      (node (ref "SW11") (pin "SW2") (pinfunction "SW2_SW2") (pintype "bidirectional"))
    )
    (net (code "59") (name "Net-(D10-PadA)") (class "Default")
      (node (ref "D10") (pin "A") (pinfunction "A_A") (pintype "passive"))
      (node (ref "SW26") (pin "SW2") (pinfunction "SW2_SW2") (pintype "bidirectional"))
    )
    (net (code "60") (name "Net-(D11-PadA)") (class "Default")
      (node (ref "D11") (pin "A") (pinfunction "A_A") (pintype "passive"))
      (node (ref "SW25") (pin "SW2") (pinfunction "SW2_SW2") (pintype "bidirectional"))
    )
    (net (code "61") (name "Net-(D12-PadA)") (class "Default")
      (node (ref "D12") (pin "A") (pinfunction "A_A") (pintype "passive"))
      (node (ref "SW24") (pin "SW2") (pinfunction "SW2_SW2") (pintype "bidirectional"))
    )
    (net (code "62") (name "Net-(D13-PadA)") (class "Default")
      (node (ref "D13") (pin "A") (pinfunction "A_A") (pintype "passive"))
      (node (ref "SW23") (pin "SW2") (pinfunction "SW2_SW2") (pintype "bidirectional"))
    )
    (net (code "63") (name "Net-(D14-PadA)") (class "Default")
      (node (ref "D14") (pin "A") (pinfunction "A_A") (pintype "passive"))
      (node (ref "SW22") (pin "SW2") (pinfunction "SW2_SW2") (pintype "bidirectional"))
    )
    (net (code "64") (name "Net-(D15-PadA)") (class "Default")
      (node (ref "D15") (pin "A") (pinfunction "A_A") (pintype "passive"))
      (node (ref "SW21") (pin "SW2") (pinfunction "SW2_SW2") (pintype "bidirectional"))
    )
    (net (code "65") (name "Net-(D16-PadA)") (class "Default")
      (node (ref "D16") (pin "A") (pinfunction "A_A") (pintype "passive"))
      (node (ref "SW56") (pin "SW2") (pinfunction "SW2_SW2") (pintype "bidirectional"))
    )
    (net (code "66") (name "Net-(D17-PadA)") (class "Default")
      (node (ref "D17") (pin "A") (pinfunction "A_A") (pintype "passive"))
      (node (ref "SW55") (pin "SW2") (pinfunction "SW2_SW2") (pintype "bidirectional"))
    )
    (net (code "67") (name "Net-(D18-PadA)") (class "Default")
      (node (ref "D18") (pin "A") (pinfunction "A_A") (pintype "passive"))
      (node (ref "SW54") (pin "SW2") (pinfunction "SW2_SW2") (pintype "bidirectional"))
    )
    (net (code "68") (name "Net-(D19-PadA)") (class "Default")
      (node (ref "D19") (pin "A") (pinfunction "A_A") (pintype "passive"))
      (node (ref "SW53") (pin "SW2") (pinfunction "SW2_SW2") (pintype "bidirectional"))
    )
    (net (code "69") (name "Net-(D20-PadA)") (class "Default")
      (node (ref "D20") (pin "A") (pinfunction "A_A") (pintype "passive"))
      (node (ref "SW52") (pin "SW2") (pinfunction "SW2_SW2") (pintype "bidirectional"))
    )
    (net (code "70") (name "Net-(D21-PadA)") (class "Default")
      (node (ref "D21") (pin "A") (pinfunction "A_A") (pintype "passive"))
      (node (ref "SW51") (pin "SW2") (pinfunction "SW2_SW2") (pintype "bidirectional"))
    )
    (net (code "71") (name "Net-(D22-PadA)") (class "Default")
      (node (ref "D22") (pin "A") (pinfunction "A_A") (pintype "passive"))
      (node (ref "SW46") (pin "SW2") (pinfunction "SW2_SW2") (pintype "bidirectional"))
    )
    (net (code "72") (name "Net-(D23-PadA)") (class "Default")
      (node (ref "D23") (pin "A") (pinfunction "A_A") (pintype "passive"))
      (node (ref "SW45") (pin "SW2") (pinfunction "SW2_SW2") (pintype "bidirectional"))
    )
    (net (code "73") (name "Net-(D24-PadA)") (class "Default")
      (node (ref "D24") (pin "A") (pinfunction "A_A") (pintype "passive"))
      (node (ref "SW44") (pin "SW2") (pinfunction "SW2_SW2") (pintype "bidirectional"))
    )
    (net (code "74") (name "Net-(D25-PadA)") (class "Default")
      (node (ref "D25") (pin "A") (pinfunction "A_A") (pintype "passive"))
      (node (ref "SW43") (pin "SW2") (pinfunction "SW2_SW2") (pintype "bidirectional"))
    )
    (net (code "75") (name "Net-(D26-PadA)") (class "Default")
      (node (ref "D26") (pin "A") (pinfunction "A_A") (pintype "passive"))
      (node (ref "SW42") (pin "SW2") (pinfunction "SW2_SW2") (pintype "bidirectional"))
    )
    (net (code "76") (name "Net-(D27-PadA)") (class "Default")
      (node (ref "D27") (pin "A") (pinfunction "A_A") (pintype "passive"))
      (node (ref "SW41") (pin "SW2") (pinfunction "SW2_SW2") (pintype "bidirectional"))
    )
    (net (code "77") (name "Net-(D28-PadA)") (class "Default")
      (node (ref "D28") (pin "A") (pinfunction "A_A") (pintype "passive"))
      (node (ref "SW36") (pin "SW2") (pinfunction "SW2_SW2") (pintype "bidirectional"))
    )
    (net (code "78") (name "Net-(D29-PadA)") (class "Default")
      (node (ref "D29") (pin "A") (pinfunction "A_A") (pintype "passive"))
      (node (ref "SW35") (pin "SW1") (pinfunction "SW1_SW1") (pintype "bidirectional"))
    )
    (net (code "79") (name "Net-(D30-PadA)") (class "Default")
      (node (ref "D30") (pin "A") (pinfunction "A_A") (pintype "passive"))
      (node (ref "SW34") (pin "SW2") (pinfunction "SW2_SW2") (pintype "bidirectional"))
    )
    (net (code "80") (name "Net-(D31-PadA)") (class "Default")
      (node (ref "D31") (pin "A") (pinfunction "A_A") (pintype "passive"))
      (node (ref "SW33") (pin "SW2") (pinfunction "SW2_SW2") (pintype "bidirectional"))
    )
    (net (code "81") (name "Net-(D32-PadA)") (class "Default")
      (node (ref "D32") (pin "A") (pinfunction "A_A") (pintype "passive"))
      (node (ref "SW32") (pin "SW2") (pinfunction "SW2_SW2") (pintype "bidirectional"))
    )
    (net (code "82") (name "Net-(D33-PadA)") (class "Default")
      (node (ref "D33") (pin "A") (pinfunction "A_A") (pintype "passive"))
      (node (ref "SW31") (pin "SW2") (pinfunction "SW2_SW2") (pintype "bidirectional"))
    )
    (net (code "83") (name "Net-(IC1A-IREF)") (class "Default")
      (node (ref "IC1") (pin "1") (pinfunction "IREF_1") (pintype "bidirectional"))
      (node (ref "R15") (pin "2") (pinfunction "2_2") (pintype "passive"))
    )
    (net (code "84") (name "Net-(IC1A-SCKI)") (class "Default")
      (node (ref "IC1") (pin "10") (pinfunction "SCKI_10") (pintype "input"))
      (node (ref "IC4") (pin "3") (pinfunction "O_3") (pintype "output"))
    )
    (net (code "85") (name "Net-(IC1A-SCKO)") (class "Default")
      (node (ref "IC1") (pin "11") (pinfunction "SCKO_11") (pintype "output"))
      (node (ref "IC2") (pin "10") (pinfunction "SCKI_10") (pintype "input"))
    )
    (net (code "86") (name "Net-(IC1A-SDTO)") (class "Default")
      (node (ref "IC1") (pin "12") (pinfunction "SDTO_12") (pintype "output"))
      (node (ref "IC2") (pin "9") (pinfunction "SDTI_9") (pintype "input"))
    )
    (net (code "87") (name "Net-(IC2A-IREF)") (class "Default")
      (node (ref "IC2") (pin "1") (pinfunction "IREF_1") (pintype "bidirectional"))
      (node (ref "R16") (pin "2") (pinfunction "2_2") (pintype "passive"))
    )
    (net (code "88") (name "Net-(IC2A-SCKO)") (class "Default")
      (node (ref "IC2") (pin "11") (pinfunction "SCKO_11") (pintype "output"))
      (node (ref "IC3") (pin "10") (pinfunction "SCKI_10") (pintype "input"))
    )
    (net (code "89") (name "Net-(IC2A-SDTO)") (class "Default")
      (node (ref "IC2") (pin "12") (pinfunction "SDTO_12") (pintype "output"))
      (node (ref "IC3") (pin "9") (pinfunction "SDTI_9") (pintype "input"))
    )
    (net (code "90") (name "Net-(IC3A-IREF)") (class "Default")
      (node (ref "IC3") (pin "1") (pinfunction "IREF_1") (pintype "bidirectional"))
      (node (ref "R17") (pin "2") (pinfunction "2_2") (pintype "passive"))
    )
    (net (code "91") (name "Net-(J1-CC1)") (class "Default")
      (node (ref "J1") (pin "A5") (pinfunction "CC1_A5") (pintype "bidirectional"))
      (node (ref "R12") (pin "2") (pinfunction "2_2") (pintype "passive"))
    )
    (net (code "92") (name "Net-(J1-CC2)") (class "Default")
      (node (ref "J1") (pin "B5") (pinfunction "CC2_B5") (pintype "bidirectional"))
      (node (ref "R11") (pin "2") (pinfunction "2_2") (pintype "passive"))
    )
    (net (code "93") (name "Net-(MOB-PadC)") (class "Default")
      (node (ref "MOB") (pin "C") (pinfunction "C_C") (pintype "passive"))
      (node (ref "R2") (pin "1") (pinfunction "1_1") (pintype "passive"))
    )
    (net (code "94") (name "Net-(U3-PROG)") (class "Default")
      (node (ref "R8") (pin "1") (pinfunction "1_1") (pintype "passive"))
      (node (ref "U3") (pin "5") (pinfunction "PROG_5") (pintype "input"))
    )
    (net (code "95") (name "Net-(U3-STAT)") (class "Default")
      (node (ref "R2") (pin "2") (pinfunction "2_2") (pintype "passive"))
      (node (ref "U3") (pin "1") (pinfunction "STAT_1") (pintype "output"))
    )
    (net (code "96") (name "Net-(U4-D+)") (class "Default")
      (node (ref "R5") (pin "2") (pinfunction "2_2") (pintype "passive"))
      (node (ref "U4") (pin "4") (pinfunction "D+_4") (pintype "bidirectional"))
    )
    (net (code "97") (name "Net-(U4-D-)") (class "Default")
      (node (ref "R4") (pin "2") (pinfunction "2_2") (pintype "passive"))
      (node (ref "U4") (pin "3") (pinfunction "D-_3") (pintype "bidirectional"))
    )
    (net (code "98") (name "Net-(U4-XTAL1)") (class "Default")
      (node (ref "U4") (pin "17") (pinfunction "XTAL1_17") (pintype "bidirectional"))
      (node (ref "Y1") (pin "1") (pinfunction "1_1") (pintype "passive"))
    )
    (net (code "99") (name "Net-(U4-XTAL2)") (class "Default")
      (node (ref "U4") (pin "16") (pinfunction "XTAL2_16") (pintype "bidirectional"))
      (node (ref "Y1") (pin "3") (pinfunction "3_3") (pintype "passive"))
    )
    (net (code "100") (name "PB0_KEYINT") (class "Default")
      (node (ref "D34") (pin "A") (pinfunction "A_A") (pintype "passive"))
      (node (ref "D35") (pin "A") (pinfunction "A_A") (pintype "passive"))
      (node (ref "D36") (pin "A") (pinfunction "A_A") (pintype "passive"))
      (node (ref "D37") (pin "A") (pinfunction "A_A") (pintype "passive"))
      (node (ref "D38") (pin "A") (pinfunction "A_A") (pintype "passive"))
      (node (ref "D39") (pin "A") (pinfunction "A_A") (pintype "passive"))
      (node (ref "U4") (pin "8") (pinfunction "PB0(SS)_8") (pintype "bidirectional"))
    )
    (net (code "101") (name "PB1_SCK") (class "Default")
      (node (ref "IC4") (pin "1") (pinfunction "I0_1") (pintype "input"))
      (node (ref "J5") (pin "3") (pinfunction "3_3") (pintype "bidirectional"))
      (node (ref "U1") (pin "4") (pinfunction "P0.21_4") (pintype "bidirectional"))
      (node (ref "U4") (pin "9") (pinfunction "PB1(SCK)_9") (pintype "bidirectional"))
    )
    (net (code "102") (name "PB2_MOSI") (class "Default")
      (node (ref "IC1") (pin "9") (pinfunction "SDTI_9") (pintype "input"))
      (node (ref "J5") (pin "4") (pinfunction "4_4") (pintype "bidirectional"))
      (node (ref "U1") (pin "6") (pinfunction "P0.23_6") (pintype "bidirectional"))
      (node (ref "U4") (pin "10") (pinfunction "PB2(MOSI)_10") (pintype "bidirectional"))
    )
    (net (code "103") (name "PB3_MISO") (class "Default")
      (node (ref "J5") (pin "1") (pinfunction "1_1") (pintype "bidirectional"))
      (node (ref "U1") (pin "5") (pinfunction "P0.22_5") (pintype "bidirectional"))
      (node (ref "U4") (pin "11") (pinfunction "PB3(MISO)_11") (pintype "bidirectional"))
    )
    (net (code "104") (name "PB4_BLE_CS") (class "Default")
      (node (ref "U1") (pin "7") (pinfunction "P0.24_7") (pintype "bidirectional"))
      (node (ref "U4") (pin "28") (pinfunction "PB4(ADC11)_28") (pintype "bidirectional"))
    )
    (net (code "105") (name "PB5_BLE_RST") (class "Default")
      (node (ref "J4") (pin "3") (pinfunction "3_3") (pintype "bidirectional"))
      (node (ref "U1") (pin "35") (pinfunction "SWDIO/NRESET_35") (pintype "bidirectional"))
      (node (ref "U4") (pin "29") (pinfunction "PB5(ADC12)_29") (pintype "bidirectional"))
    )
    (net (code "106") (name "PB6_BLE_IRQ") (class "Default")
      (node (ref "U1") (pin "8") (pinfunction "P0.25_8") (pintype "bidirectional"))
      (node (ref "U4") (pin "30") (pinfunction "PB6(ADC13)_30") (pintype "bidirectional"))
    )
    (net (code "107") (name "PB7_LED_SS") (class "Default")
      (node (ref "IC4") (pin "2") (pinfunction "I1_2") (pintype "input"))
      (node (ref "U4") (pin "12") (pinfunction "PB7_12") (pintype "bidirectional"))
    )
    (net (code "108") (name "PC6") (class "Default")
      (node (ref "U4") (pin "31") (pinfunction "PC6_31") (pintype "bidirectional"))
    )
    (net (code "109") (name "PC7") (class "Default")
      (node (ref "U4") (pin "32") (pinfunction "PC7_32") (pintype "bidirectional"))
    )
    (net (code "110") (name "PD0_SCL") (class "Default")
      (node (ref "J2") (pin "RING1") (pinfunction "RING1_RING1") (pintype "bidirectional"))
      (node (ref "J3") (pin "RING1") (pinfunction "RING1_RING1") (pintype "bidirectional"))
      (node (ref "R13") (pin "2") (pinfunction "2_2") (pintype "passive"))
      (node (ref "U4") (pin "18") (pinfunction "PD0(SCL)_18") (pintype "bidirectional"))
    )
    (net (code "111") (name "PD1_SDA") (class "Default")
      (node (ref "J2") (pin "TIP") (pinfunction "TIP_TIP") (pintype "bidirectional"))
      (node (ref "J3") (pin "TIP") (pinfunction "TIP_TIP") (pintype "bidirectional"))
      (node (ref "R14") (pin "2") (pinfunction "2_2") (pintype "passive"))
      (node (ref "U4") (pin "19") (pinfunction "PD1(SDA)_19") (pintype "bidirectional"))
    )
    (net (code "112") (name "PD2_ROW3") (class "Default")
      (node (ref "D28") (pin "C") (pinfunction "C_C") (pintype "passive"))
      (node (ref "D29") (pin "C") (pinfunction "C_C") (pintype "passive"))
      (node (ref "D30") (pin "C") (pinfunction "C_C") (pintype "passive"))
      (node (ref "D31") (pin "C") (pinfunction "C_C") (pintype "passive"))
      (node (ref "D32") (pin "C") (pinfunction "C_C") (pintype "passive"))
      (node (ref "D33") (pin "C") (pinfunction "C_C") (pintype "passive"))
      (node (ref "U4") (pin "20") (pinfunction "PD2(RX)_20") (pintype "bidirectional"))
    )
    (net (code "113") (name "PD3_ROW2") (class "Default")
      (node (ref "D10") (pin "C") (pinfunction "C_C") (pintype "passive"))
      (node (ref "D11") (pin "C") (pinfunction "C_C") (pintype "passive"))
      (node (ref "D12") (pin "C") (pinfunction "C_C") (pintype "passive"))
      (node (ref "D13") (pin "C") (pinfunction "C_C") (pintype "passive"))
      (node (ref "D14") (pin "C") (pinfunction "C_C") (pintype "passive"))
      (node (ref "D15") (pin "C") (pinfunction "C_C") (pintype "passive"))
      (node (ref "U4") (pin "21") (pinfunction "PD3(TX)_21") (pintype "bidirectional"))
    )
    (net (code "114") (name "PD4_ROW5") (class "Default")
      (node (ref "D16") (pin "C") (pinfunction "C_C") (pintype "passive"))
      (node (ref "D17") (pin "C") (pinfunction "C_C") (pintype "passive"))
      (node (ref "D18") (pin "C") (pinfunction "C_C") (pintype "passive"))
      (node (ref "D19") (pin "C") (pinfunction "C_C") (pintype "passive"))
      (node (ref "D20") (pin "C") (pinfunction "C_C") (pintype "passive"))
      (node (ref "D21") (pin "C") (pinfunction "C_C") (pintype "passive"))
      (node (ref "U4") (pin "25") (pinfunction "PD4(ADC8)_25") (pintype "bidirectional"))
    )
    (net (code "115") (name "PD6_ROW4") (class "Default")
      (node (ref "D22") (pin "C") (pinfunction "C_C") (pintype "passive"))
      (node (ref "D23") (pin "C") (pinfunction "C_C") (pintype "passive"))
      (node (ref "D24") (pin "C") (pinfunction "C_C") (pintype "passive"))
      (node (ref "D25") (pin "C") (pinfunction "C_C") (pintype "passive"))
      (node (ref "D26") (pin "C") (pinfunction "C_C") (pintype "passive"))
      (node (ref "D27") (pin "C") (pinfunction "C_C") (pintype "passive"))
      (node (ref "U4") (pin "26") (pinfunction "PD6(ADC9)_26") (pintype "bidirectional"))
    )
    (net (code "116") (name "PD7_ROW1") (class "Default")
      (node (ref "D3") (pin "C") (pinfunction "C_C") (pintype "passive"))
      (node (ref "D5") (pin "C") (pinfunction "C_C") (pintype "passive"))
      (node (ref "D6") (pin "C") (pinfunction "C_C") (pintype "passive"))
      (node (ref "D7") (pin "C") (pinfunction "C_C") (pintype "passive"))
      (node (ref "D8") (pin "C") (pinfunction "C_C") (pintype "passive"))
      (node (ref "D9") (pin "C") (pinfunction "C_C") (pintype "passive"))
      (node (ref "U4") (pin "27") (pinfunction "PD7(ADC10)_27") (pintype "bidirectional"))
    )
    (net (code "117") (name "PE6") (class "Default")
      (node (ref "U4") (pin "1") (pinfunction "PE6_1") (pintype "bidirectional"))
    )
    (net (code "118") (name "PF0_COL6") (class "Default")
      (node (ref "D34") (pin "C") (pinfunction "C_C") (pintype "passive"))
      (node (ref "SW16") (pin "SW1") (pinfunction "SW1_SW1") (pintype "bidirectional"))
      (node (ref "SW26") (pin "SW1") (pinfunction "SW1_SW1") (pintype "bidirectional"))
      (node (ref "SW36") (pin "SW1") (pinfunction "SW1_SW1") (pintype "bidirectional"))
      (node (ref "SW46") (pin "SW1") (pinfunction "SW1_SW1") (pintype "bidirectional"))
      (node (ref "SW56") (pin "SW1") (pinfunction "SW1_SW1") (pintype "bidirectional"))
      (node (ref "U4") (pin "41") (pinfunction "PF0(ADC0)_41") (pintype "bidirectional"))
    )
    (net (code "119") (name "PF1_COL5") (class "Default")
      (node (ref "D35") (pin "C") (pinfunction "C_C") (pintype "passive"))
      (node (ref "SW15") (pin "SW1") (pinfunction "SW1_SW1") (pintype "bidirectional"))
      (node (ref "SW25") (pin "SW1") (pinfunction "SW1_SW1") (pintype "bidirectional"))
      (node (ref "SW35") (pin "SW2") (pinfunction "SW2_SW2") (pintype "bidirectional"))
      (node (ref "SW45") (pin "SW1") (pinfunction "SW1_SW1") (pintype "bidirectional"))
      (node (ref "SW55") (pin "SW1") (pinfunction "SW1_SW1") (pintype "bidirectional"))
      (node (ref "U4") (pin "40") (pinfunction "PF1(ADC1)_40") (pintype "bidirectional"))
    )
    (net (code "120") (name "PF4_COL4") (class "Default")
      (node (ref "D36") (pin "C") (pinfunction "C_C") (pintype "passive"))
      (node (ref "SW14") (pin "SW1") (pinfunction "SW1_SW1") (pintype "bidirectional"))
      (node (ref "SW24") (pin "SW1") (pinfunction "SW1_SW1") (pintype "bidirectional"))
      (node (ref "SW34") (pin "SW1") (pinfunction "SW1_SW1") (pintype "bidirectional"))
      (node (ref "SW44") (pin "SW1") (pinfunction "SW1_SW1") (pintype "bidirectional"))
      (node (ref "SW54") (pin "SW1") (pinfunction "SW1_SW1") (pintype "bidirectional"))
      (node (ref "U4") (pin "39") (pinfunction "PF4(ADC4)_39") (pintype "bidirectional"))
    )
    (net (code "121") (name "PF5_COL3") (class "Default")
      (node (ref "D37") (pin "C") (pinfunction "C_C") (pintype "passive"))
      (node (ref "SW13") (pin "SW2") (pinfunction "SW2_SW2") (pintype "bidirectional"))
      (node (ref "SW23") (pin "SW1") (pinfunction "SW1_SW1") (pintype "bidirectional"))
      (node (ref "SW33") (pin "SW1") (pinfunction "SW1_SW1") (pintype "bidirectional"))
      (node (ref "SW43") (pin "SW1") (pinfunction "SW1_SW1") (pintype "bidirectional"))
      (node (ref "SW53") (pin "SW1") (pinfunction "SW1_SW1") (pintype "bidirectional"))
      (node (ref "U4") (pin "38") (pinfunction "PF5(ADC5)_38") (pintype "bidirectional"))
    )
    (net (code "122") (name "PF6_COL2") (class "Default")
      (node (ref "D38") (pin "C") (pinfunction "C_C") (pintype "passive"))
      (node (ref "SW12") (pin "SW1") (pinfunction "SW1_SW1") (pintype "bidirectional"))
      (node (ref "SW22") (pin "SW1") (pinfunction "SW1_SW1") (pintype "bidirectional"))
      (node (ref "SW32") (pin "SW1") (pinfunction "SW1_SW1") (pintype "bidirectional"))
      (node (ref "SW42") (pin "SW1") (pinfunction "SW1_SW1") (pintype "bidirectional"))
      (node (ref "SW52") (pin "SW1") (pinfunction "SW1_SW1") (pintype "bidirectional"))
      (node (ref "U4") (pin "37") (pinfunction "PF6(ADC6)_37") (pintype "bidirectional"))
    )
    (net (code "123") (name "PF7_COL1") (class "Default")
      (node (ref "D39") (pin "C") (pinfunction "C_C") (pintype "passive"))
      (node (ref "SW11") (pin "SW1") (pinfunction "SW1_SW1") (pintype "bidirectional"))
      (node (ref "SW21") (pin "SW1") (pinfunction "SW1_SW1") (pintype "bidirectional"))
      (node (ref "SW31") (pin "SW1") (pinfunction "SW1_SW1") (pintype "bidirectional"))
      (node (ref "SW41") (pin "SW1") (pinfunction "SW1_SW1") (pintype "bidirectional"))
      (node (ref "SW51") (pin "SW1") (pinfunction "SW1_SW1") (pintype "bidirectional"))
      (node (ref "U4") (pin "36") (pinfunction "PF7(ADC7)_36") (pintype "bidirectional"))
    )
    (net (code "124") (name "RST") (class "Default")
      (node (ref "J5") (pin "5") (pinfunction "5_5") (pintype "bidirectional"))
      (node (ref "S2") (pin "1") (pinfunction "1_1") (pintype "passive"))
      (node (ref "S2") (pin "2") (pinfunction "2_2") (pintype "passive"))
      (node (ref "U4") (pin "13") (pinfunction "~{RESET}_13") (pintype "bidirectional"))
    )
    (net (code "125") (name "SWCLK") (class "Default")
      (node (ref "J4") (pin "1") (pinfunction "1_1") (pintype "bidirectional"))
      (node (ref "U1") (pin "36") (pinfunction "SWCLK_36") (pintype "bidirectional"))
    )
    (net (code "126") (name "VBAT") (class "Default")
      (node (ref "C3") (pin "1") (pinfunction "1_1") (pintype "passive"))
      (node (ref "CN1") (pin "1") (pinfunction "2_1") (pintype "passive"))
      (node (ref "D4") (pin "A") (pinfunction "A_A") (pintype "passive"))
      (node (ref "R3") (pin "1") (pinfunction "1_1") (pintype "passive"))
      (node (ref "U3") (pin "3") (pinfunction "VBAT_3") (pintype "power_in"))
    )
    (net (code "127") (name "VBUS") (class "Default")
      (node (ref "C6") (pin "1") (pinfunction "1_1") (pintype "passive"))
      (node (ref "D4") (pin "C") (pinfunction "C_C") (pintype "passive"))
      (node (ref "J1") (pin "A4") (pinfunction "V+_A4") (pintype "power_in"))
      (node (ref "J1") (pin "A9") (pinfunction "V+_A9") (pintype "power_in"))
      (node (ref "J1") (pin "B4") (pinfunction "V+_B4") (pintype "power_in"))
      (node (ref "J1") (pin "B9") (pinfunction "V+_B9") (pintype "power_in"))
      (node (ref "MOB") (pin "A") (pinfunction "A_A") (pintype "passive"))
      (node (ref "R9") (pin "1") (pinfunction "1_1") (pintype "passive"))
      (node (ref "U2") (pin "1") (pinfunction "IN_1") (pintype "power_in"))
      (node (ref "U3") (pin "4") (pinfunction "VDD_4") (pintype "power_in"))
      (node (ref "U4") (pin "7") (pinfunction "VBUS_7") (pintype "bidirectional"))
    )
    (net (code "128") (name "unconnected-(IC1A-OUTB0-Pad5)") (class "Default")
      (node (ref "IC1") (pin "5") (pinfunction "OUTB0_5") (pintype "open_collector"))
    )
    (net (code "129") (name "unconnected-(IC1A-OUTG1-Pad7)") (class "Default")
      (node (ref "IC1") (pin "7") (pinfunction "OUTG1_7") (pintype "open_collector"))
    )
    (net (code "130") (name "unconnected-(IC1A-OUTR1-Pad6)") (class "Default")
      (node (ref "IC1") (pin "6") (pinfunction "OUTR1_6") (pintype "open_collector"))
    )
    (net (code "131") (name "unconnected-(IC3A-OUTB2-Pad15)") (class "Default")
      (node (ref "IC3") (pin "15") (pinfunction "OUTB2_15") (pintype "open_collector"))
    )
    (net (code "132") (name "unconnected-(IC3A-OUTG3-Pad17)") (class "Default")
      (node (ref "IC3") (pin "17") (pinfunction "OUTG3_17") (pintype "open_collector"))
    )
    (net (code "133") (name "unconnected-(IC3A-OUTR3-Pad16)") (class "Default")
      (node (ref "IC3") (pin "16") (pinfunction "OUTR3_16") (pintype "open_collector"))
    )
    (net (code "134") (name "unconnected-(IC3A-SCKO-Pad11)") (class "Default")
      (node (ref "IC3") (pin "11") (pinfunction "SCKO_11") (pintype "output"))
    )
    (net (code "135") (name "unconnected-(IC3A-SDTO-Pad12)") (class "Default")
      (node (ref "IC3") (pin "12") (pinfunction "SDTO_12") (pintype "output"))
    )
    (net (code "136") (name "unconnected-(J1-RX1+-PadB11)") (class "Default")
      (node (ref "J1") (pin "B11") (pinfunction "RX1+_B11") (pintype "input"))
    )
    (net (code "137") (name "unconnected-(J1-RX1--PadB10)") (class "Default")
      (node (ref "J1") (pin "B10") (pinfunction "RX1-_B10") (pintype "input"))
    )
    (net (code "138") (name "unconnected-(J1-RX2+-PadA11)") (class "Default")
      (node (ref "J1") (pin "A11") (pinfunction "RX2+_A11") (pintype "input"))
    )
    (net (code "139") (name "unconnected-(J1-RX2--PadA10)") (class "Default")
      (node (ref "J1") (pin "A10") (pinfunction "RX2-_A10") (pintype "input"))
    )
    (net (code "140") (name "unconnected-(J1-SBU1-PadA8)") (class "Default")
      (node (ref "J1") (pin "A8") (pinfunction "SBU1_A8") (pintype "bidirectional"))
    )
    (net (code "141") (name "unconnected-(J1-SBU2-PadB8)") (class "Default")
      (node (ref "J1") (pin "B8") (pinfunction "SBU2_B8") (pintype "bidirectional"))
    )
    (net (code "142") (name "unconnected-(J1-TX1+-PadA2)") (class "Default")
      (node (ref "J1") (pin "A2") (pinfunction "TX1+_A2") (pintype "output"))
    )
    (net (code "143") (name "unconnected-(J1-TX1--PadA3)") (class "Default")
      (node (ref "J1") (pin "A3") (pinfunction "TX1-_A3") (pintype "output"))
    )
    (net (code "144") (name "unconnected-(J1-TX2+-PadB2)") (class "Default")
      (node (ref "J1") (pin "B2") (pinfunction "TX2+_B2") (pintype "output"))
    )
    (net (code "145") (name "unconnected-(J1-TX2--PadB3)") (class "Default")
      (node (ref "J1") (pin "B3") (pinfunction "TX2-_B3") (pintype "output"))
    )
    (net (code "146") (name "unconnected-(S1-S-Pad3)") (class "Default")
      (node (ref "S1") (pin "3") (pinfunction "S_3") (pintype "passive"))
    )
    (net (code "147") (name "unconnected-(U1-P0.00{slash}AREF0-Pad17)") (class "Default")
      (node (ref "U1") (pin "17") (pinfunction "P0.00/AREF0_17") (pintype "bidirectional"))
    )
    (net (code "148") (name "unconnected-(U1-P0.01{slash}AIN2-Pad18)") (class "Default")
      (node (ref "U1") (pin "18") (pinfunction "P0.01/AIN2_18") (pintype "bidirectional"))
    )
    (net (code "149") (name "unconnected-(U1-P0.02{slash}AIN3-Pad19)") (class "Default")
      (node (ref "U1") (pin "19") (pinfunction "P0.02/AIN3_19") (pintype "bidirectional"))
    )
    (net (code "150") (name "unconnected-(U1-P0.03{slash}AIN4-Pad20)") (class "Default")
      (node (ref "U1") (pin "20") (pinfunction "P0.03/AIN4_20") (pintype "bidirectional"))
    )
    (net (code "151") (name "unconnected-(U1-P0.04{slash}AIN5-Pad21)") (class "Default")
      (node (ref "U1") (pin "21") (pinfunction "P0.04/AIN5_21") (pintype "bidirectional"))
    )
    (net (code "152") (name "unconnected-(U1-P0.05{slash}AIN6-Pad22)") (class "Default")
      (node (ref "U1") (pin "22") (pinfunction "P0.05/AIN6_22") (pintype "bidirectional"))
    )
    (net (code "153") (name "unconnected-(U1-P0.06{slash}AIN7{slash}AREF1-Pad23)") (class "Default")
      (node (ref "U1") (pin "23") (pinfunction "P0.06/AIN7/AREF1_23") (pintype "bidirectional"))
    )
    (net (code "154") (name "unconnected-(U1-P0.08-Pad26)") (class "Default")
      (node (ref "U1") (pin "26") (pinfunction "P0.08_26") (pintype "bidirectional"))
    )
    (net (code "155") (name "unconnected-(U1-P0.09-Pad27)") (class "Default")
      (node (ref "U1") (pin "27") (pinfunction "P0.09_27") (pintype "bidirectional"))
    )
    (net (code "156") (name "unconnected-(U1-P0.10-Pad28)") (class "Default")
      (node (ref "U1") (pin "28") (pinfunction "P0.10_28") (pintype "bidirectional"))
    )
    (net (code "157") (name "unconnected-(U1-P0.11-Pad29)") (class "Default")
      (node (ref "U1") (pin "29") (pinfunction "P0.11_29") (pintype "bidirectional"))
    )
    (net (code "158") (name "unconnected-(U1-P0.12-Pad30)") (class "Default")
      (node (ref "U1") (pin "30") (pinfunction "P0.12_30") (pintype "bidirectional"))
    )
    (net (code "159") (name "unconnected-(U1-P0.13-Pad31)") (class "Default")
      (node (ref "U1") (pin "31") (pinfunction "P0.13_31") (pintype "bidirectional"))
    )
    (net (code "160") (name "unconnected-(U1-P0.14-Pad32)") (class "Default")
      (node (ref "U1") (pin "32") (pinfunction "P0.14_32") (pintype "bidirectional"))
    )
    (net (code "161") (name "unconnected-(U1-P0.15-Pad33)") (class "Default")
      (node (ref "U1") (pin "33") (pinfunction "P0.15_33") (pintype "bidirectional"))
    )
    (net (code "162") (name "unconnected-(U1-P0.17-Pad37)") (class "Default")
      (node (ref "U1") (pin "37") (pinfunction "P0.17_37") (pintype "bidirectional"))
    )
    (net (code "163") (name "unconnected-(U1-P0.20-Pad40)") (class "Default")
      (node (ref "U1") (pin "40") (pinfunction "P0.20_40") (pintype "bidirectional"))
    )
    (net (code "164") (name "unconnected-(U1-P0.26{slash}AIN0{slash}XL2-Pad9)") (class "Default")
      (node (ref "U1") (pin "9") (pinfunction "P0.26/AIN0/XL2_9") (pintype "bidirectional"))
    )
    (net (code "165") (name "unconnected-(U1-P0.27{slash}AIN1{slash}XL1-Pad10)") (class "Default")
      (node (ref "U1") (pin "10") (pinfunction "P0.27/AIN1/XL1_10") (pintype "bidirectional"))
    )
    (net (code "166") (name "unconnected-(U1-P0.28-Pad11)") (class "Default")
      (node (ref "U1") (pin "11") (pinfunction "P0.28_11") (pintype "bidirectional"))
    )
    (net (code "167") (name "unconnected-(U1-P0.29-Pad12)") (class "Default")
      (node (ref "U1") (pin "12") (pinfunction "P0.29_12") (pintype "bidirectional"))
    )
    (net (code "168") (name "unconnected-(U2-P4-Pad4)") (class "Default")
      (node (ref "U2") (pin "4") (pinfunction "P4_4") (pintype "bidirectional"))
    )
    (net (code "169") (name "unconnected-(U4-PD5-Pad22)") (class "Default")
      (node (ref "U4") (pin "22") (pinfunction "PD5_22") (pintype "bidirectional"))
    )
    (net (code "170") (name "unconnected-(U4-UVCC-Pad2)") (class "Default")
      (node (ref "U4") (pin "2") (pinfunction "UVCC_2") (pintype "bidirectional"))
    )
  )
)
